# PP.net
KiCad netlist of a schematic drawn in Altium Designer
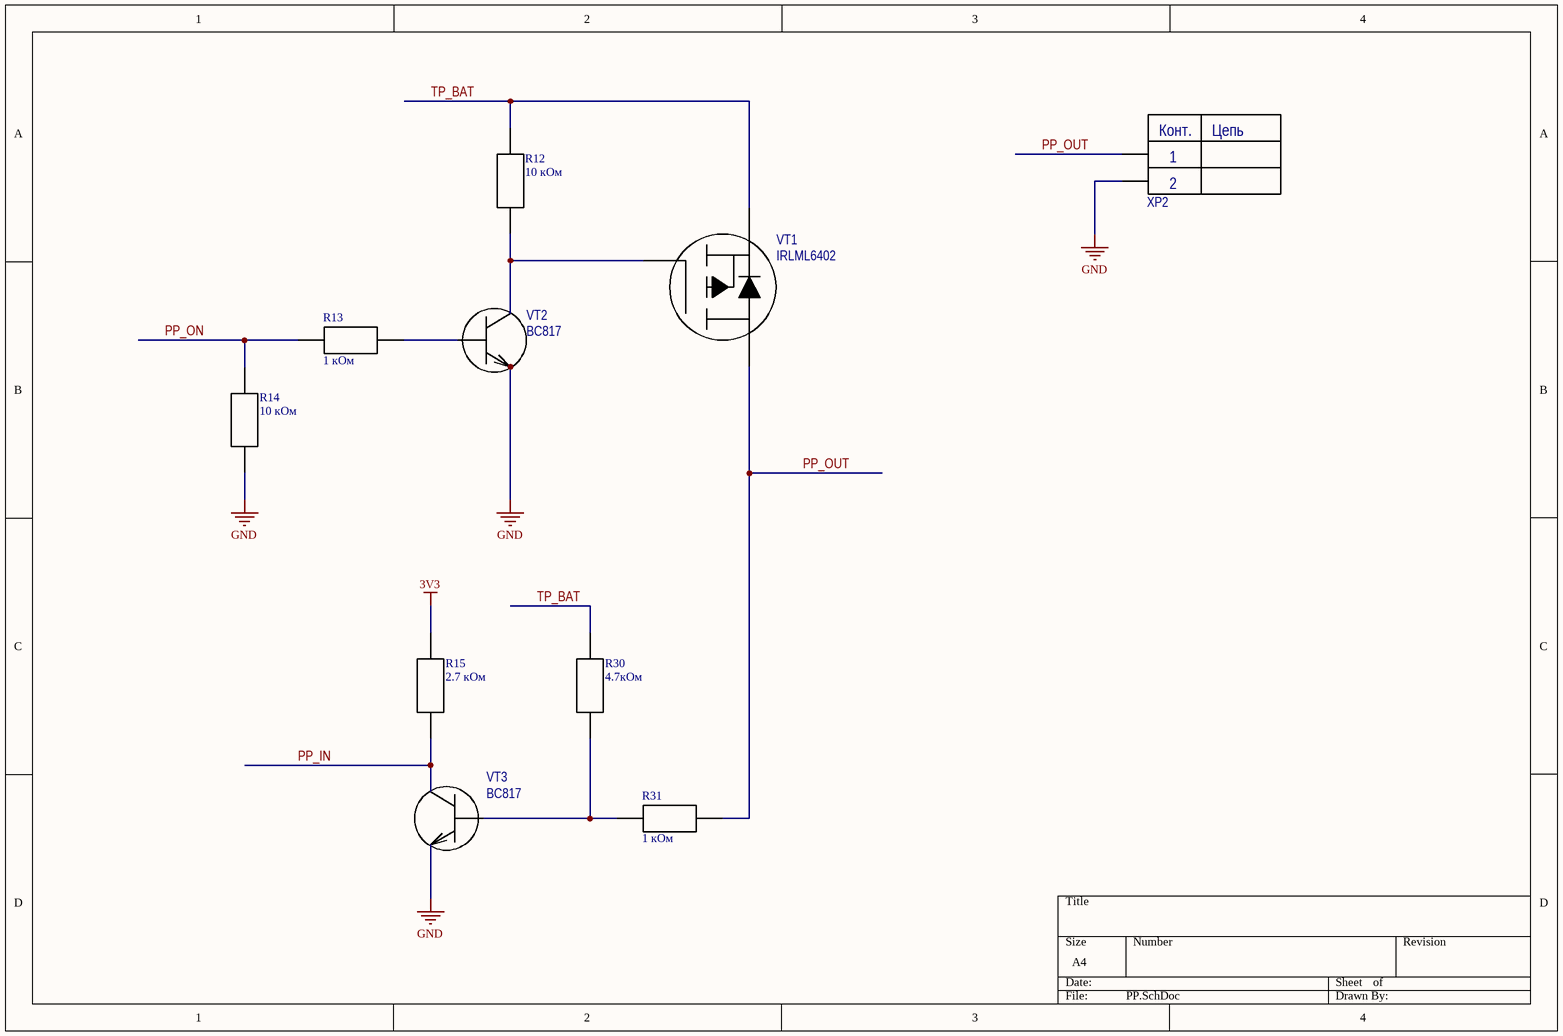
[diagram p0: PP.SchDoc]

(export (version "E")
  (design (tool "Eeschema 10.0.6"))
  (components
    (comp (ref "R12") (value "10 кОм") (footprint "RES 0805") (libsource (lib "my_lib") (part "RES 0805")))
    (comp (ref "R13") (value "1 кОм") (footprint "RES 0805") (libsource (lib "my_lib") (part "RES 0805")))
    (comp (ref "R14") (value "10 кОм") (footprint "RES 0805") (libsource (lib "my_lib") (part "RES 0805")))
    (comp (ref "R15") (value "2.7 кОм") (footprint "RES 0805") (libsource (lib "my_lib") (part "RES 0805")))
    (comp (ref "R30") (value "4.7кОм") (footprint "RES 0805") (libsource (lib "my_lib") (part "RES 0805")))
    (comp (ref "R31") (value "1 кОм") (footprint "RES 0805") (libsource (lib "my_lib") (part "RES 0805")))
    (comp (ref "VT1") (value "IRLML6402") (footprint "SOT-23") (libsource (lib "my_lib") (part "IRLML6402")))
    (comp (ref "VT2")
      (value "BC817")
      (footprint "SOT-23")
      (description "NPN general-purpose transistor")
      (fields (field (name "MANUFACTURER") "NXP"))
      (libsource (lib "my_lib") (part "BC817"))
    )
    (comp (ref "VT3")
      (value "BC817")
      (footprint "SOT-23")
      (description "NPN general-purpose transistor")
      (fields (field (name "MANUFACTURER") "NXP"))
      (libsource (lib "my_lib") (part "BC817"))
    )
    (comp (ref "XP2")
      (value "PLS-2")
      (footprint "PLS-2")
      (description "PLS connector")
      (fields (field (name "MANUFACTURER") "NONAME"))
      (libsource (lib "my_lib") (part "PLS-2"))
    )
  )
  (nets
    (net (code "1") (name "/PP_IN") (class "Default")
      (node (ref "R15") (pin "2") (pinfunction "2_2") (pintype "passive"))
      (node (ref "VT3") (pin "3") (pinfunction "C_3") (pintype "passive"))
    )
    (net (code "2") (name "/PP_ON") (class "Default")
      (node (ref "R13") (pin "2") (pinfunction "2_2") (pintype "passive"))
      (node (ref "R14") (pin "1") (pinfunction "1_1") (pintype "passive"))
    )
    (net (code "3") (name "/PP_OUT") (class "Default")
      (node (ref "R31") (pin "2") (pinfunction "2_2") (pintype "passive"))
      (node (ref "VT1") (pin "3") (pinfunction "D_3") (pintype "passive"))
      (node (ref "XP2") (pin "1") (pinfunction "1_1") (pintype "passive"))
    )
    (net (code "4") (name "/TP_BAT") (class "Default")
      (node (ref "R12") (pin "1") (pinfunction "1_1") (pintype "passive"))
      (node (ref "R30") (pin "1") (pinfunction "1_1") (pintype "passive"))
      (node (ref "VT1") (pin "2") (pinfunction "S_2") (pintype "passive"))
    )
    (net (code "5") (name "3V3") (class "Default")
      (node (ref "R15") (pin "1") (pinfunction "1_1") (pintype "passive"))
    )
    (net (code "6") (name "GND") (class "Default")
      (node (ref "R14") (pin "2") (pinfunction "2_2") (pintype "passive"))
      (node (ref "VT2") (pin "2") (pinfunction "E_2") (pintype "passive"))
      (node (ref "VT3") (pin "2") (pinfunction "E_2") (pintype "passive"))
      (node (ref "XP2") (pin "2") (pinfunction "2_2") (pintype "passive"))
    )
    (net (code "7") (name "Net-(VT1-G)") (class "Default")
      (node (ref "R12") (pin "2") (pinfunction "2_2") (pintype "passive"))
      (node (ref "VT1") (pin "1") (pinfunction "G_1") (pintype "passive"))
      (node (ref "VT2") (pin "3") (pinfunction "C_3") (pintype "passive"))
    )
    (net (code "8") (name "Net-(VT2-B)") (class "Default")
      (node (ref "R13") (pin "1") (pinfunction "1_1") (pintype "passive"))
      (node (ref "VT2") (pin "1") (pinfunction "B_1") (pintype "passive"))
    )
    (net (code "9") (name "Net-(VT3-B)") (class "Default")
      (node (ref "R30") (pin "2") (pinfunction "2_2") (pintype "passive"))
      (node (ref "R31") (pin "1") (pinfunction "1_1") (pintype "passive"))
      (node (ref "VT3") (pin "1") (pinfunction "B_1") (pintype "passive"))
    )
  )
)
